# AD8402_WeinBridge_DCO.net
KiCad netlist of a schematic drawn in EAGLE
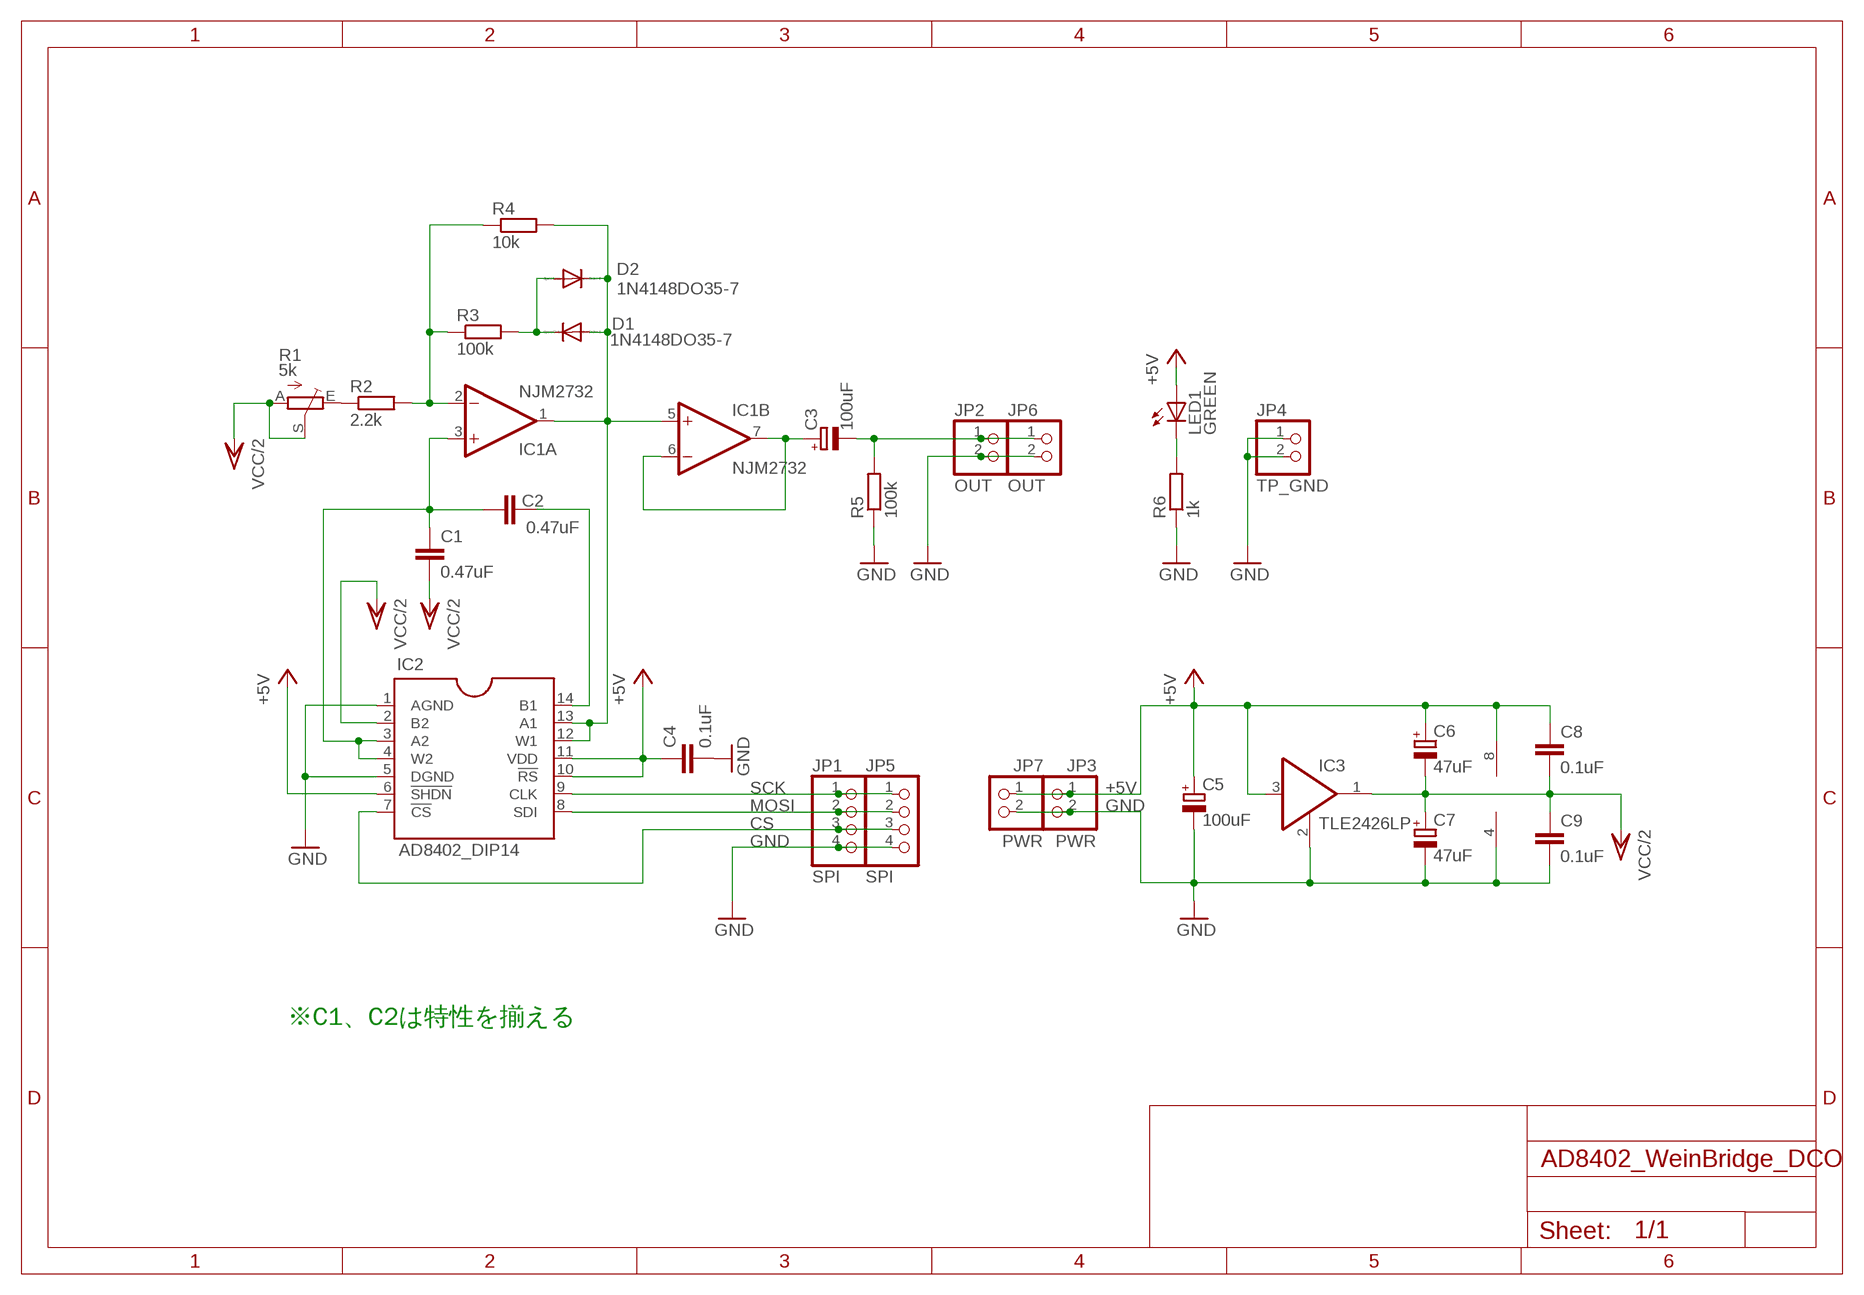
[diagram p0: schematic, sheet 1]

(export (version "E")
  (design (tool "Eeschema 10.0.6"))
  (components
    (comp (ref "C1")
      (value "0.47uF")
      (footprint "eagle-import:C050-035X075")
      (libsource (lib "eagle-import") (part "C-EU050-035X075"))
    )
    (comp (ref "C2")
      (value "0.47uF")
      (footprint "eagle-import:C050-035X075")
      (libsource (lib "eagle-import") (part "C-EU050-035X075"))
    )
    (comp (ref "C3")
      (value "100uF")
      (footprint "eagle-import:E2,5-7")
      (libsource (lib "eagle-import") (part "CPOL-EUE2.5-7"))
    )
    (comp (ref "C4")
      (value "0.1uF")
      (footprint "eagle-import:C025-024X044")
      (libsource (lib "eagle-import") (part "C-EU025-024X044"))
    )
    (comp (ref "C5")
      (value "100uF")
      (footprint "eagle-import:SANYO-OSCON_C6")
      (libsource (lib "eagle-import") (part "CPOL-EUSANYO_C6"))
    )
    (comp (ref "C6")
      (value "47uF")
      (footprint "eagle-import:E2,5-6")
      (libsource (lib "eagle-import") (part "CPOL-EUE2.5-6"))
    )
    (comp (ref "C7")
      (value "47uF")
      (footprint "eagle-import:E2,5-6")
      (libsource (lib "eagle-import") (part "CPOL-EUE2.5-6"))
    )
    (comp (ref "C8")
      (value "0.1uF")
      (footprint "eagle-import:C025-024X044")
      (libsource (lib "eagle-import") (part "C-EU025-024X044"))
    )
    (comp (ref "C9")
      (value "0.1uF")
      (footprint "eagle-import:C025-024X044")
      (libsource (lib "eagle-import") (part "C-EU025-024X044"))
    )
    (comp (ref "D1")
      (value "1N4148DO35-7")
      (footprint "eagle-import:DO35-7")
      (libsource (lib "eagle-import") (part "1N4148DO35-7"))
    )
    (comp (ref "D2")
      (value "1N4148DO35-7")
      (footprint "eagle-import:DO35-7")
      (libsource (lib "eagle-import") (part "1N4148DO35-7"))
    )
    (comp (ref "IC1")
      (value "NJM2732")
      (footprint "eagle-import:DIL08")
      (libsource (lib "eagle-import") (part "4558NLM"))
    )
    (comp (ref "IC2")
      (value "AD8402_DIP14")
      (footprint "eagle-import:AD8402_DIP14")
      (libsource (lib "eagle-import") (part "AD8402_DIP14"))
    )
    (comp (ref "IC3")
      (value "TLE2426LP")
      (footprint "eagle-import:TO226AA")
      (libsource (lib "eagle-import") (part "TLE2426LP"))
    )
    (comp (ref "JP1")
      (value "SPI")
      (footprint "eagle-import:1X04")
      (libsource (lib "eagle-import") (part "PINHD-1X4"))
    )
    (comp (ref "JP2")
      (value "OUT")
      (footprint "eagle-import:1X02")
      (libsource (lib "eagle-import") (part "PINHD-1X2"))
    )
    (comp (ref "JP3")
      (value "PWR")
      (footprint "eagle-import:1X02")
      (libsource (lib "eagle-import") (part "PINHD-1X2"))
    )
    (comp (ref "JP4")
      (value "TP_GND")
      (footprint "eagle-import:1X02")
      (libsource (lib "eagle-import") (part "PINHD-1X2"))
    )
    (comp (ref "JP5")
      (value "SPI")
      (footprint "eagle-import:1X04")
      (libsource (lib "eagle-import") (part "PINHD-1X4"))
    )
    (comp (ref "JP6")
      (value "OUT")
      (footprint "eagle-import:1X02")
      (libsource (lib "eagle-import") (part "PINHD-1X2"))
    )
    (comp (ref "JP7")
      (value "PWR")
      (footprint "eagle-import:1X02")
      (libsource (lib "eagle-import") (part "PINHD-1X2"))
    )
    (comp (ref "LED1")
      (value "GREEN")
      (footprint "eagle-import:LED3MM")
      (libsource (lib "eagle-import") (part "LED3MM"))
    )
    (comp (ref "R1")
      (value "5k")
      (footprint "eagle-import:B25P")
      (libsource (lib "eagle-import") (part "TRIM_EU-B25P"))
    )
    (comp (ref "R2")
      (value "2.2k")
      (footprint "eagle-import:0207_7")
      (libsource (lib "eagle-import") (part "R-EU_0207/7"))
    )
    (comp (ref "R3")
      (value "100k")
      (footprint "eagle-import:0207_7")
      (libsource (lib "eagle-import") (part "R-EU_0207/7"))
    )
    (comp (ref "R4")
      (value "10k")
      (footprint "eagle-import:0207_7")
      (libsource (lib "eagle-import") (part "R-EU_0207/7"))
    )
    (comp (ref "R5")
      (value "100k")
      (footprint "eagle-import:0207_7")
      (libsource (lib "eagle-import") (part "R-EU_0207/7"))
    )
    (comp (ref "R6")
      (value "1k")
      (footprint "eagle-import:0207_7")
      (libsource (lib "eagle-import") (part "R-EU_0207/7"))
    )
  )
  (nets
    (net (code "1") (name "+5V") (class "Default")
      (node (ref "C4") (pin "1") (pinfunction "1_1") (pintype "passive"))
      (node (ref "C5") (pin "+") (pinfunction "+_+") (pintype "passive"))
      (node (ref "C6") (pin "+") (pinfunction "+_+") (pintype "passive"))
      (node (ref "C8") (pin "1") (pinfunction "1_1") (pintype "passive"))
      (node (ref "IC1") (pin "8") (pinfunction "V+_8") (pintype "power_in"))
      (node (ref "IC2") (pin "10") (pinfunction "~{RS}_10") (pintype "input"))
      (node (ref "IC2") (pin "11") (pinfunction "VDD_11") (pintype "power_in"))
      (node (ref "IC2") (pin "6") (pinfunction "~{SHDN}_6") (pintype "input"))
      (node (ref "IC3") (pin "3") (pinfunction "I_3") (pintype "input"))
      (node (ref "JP3") (pin "1") (pinfunction "1_1") (pintype "passive"))
      (node (ref "JP7") (pin "1") (pinfunction "1_1") (pintype "passive"))
      (node (ref "LED1") (pin "A") (pinfunction "A_A") (pintype "passive"))
    )
    (net (code "2") (name "/CS") (class "Default")
      (node (ref "IC2") (pin "7") (pinfunction "~{CS}_7") (pintype "input"))
      (node (ref "JP1") (pin "3") (pinfunction "3_3") (pintype "passive"))
      (node (ref "JP5") (pin "3") (pinfunction "3_3") (pintype "passive"))
    )
    (net (code "3") (name "/MOSI") (class "Default")
      (node (ref "IC2") (pin "8") (pinfunction "SDI_8") (pintype "input"))
      (node (ref "JP1") (pin "2") (pinfunction "2_2") (pintype "passive"))
      (node (ref "JP5") (pin "2") (pinfunction "2_2") (pintype "passive"))
    )
    (net (code "4") (name "/SCK") (class "Default")
      (node (ref "IC2") (pin "9") (pinfunction "CLK_9") (pintype "input"))
      (node (ref "JP1") (pin "1") (pinfunction "1_1") (pintype "passive"))
      (node (ref "JP5") (pin "1") (pinfunction "1_1") (pintype "passive"))
    )
    (net (code "5") (name "GND") (class "Default")
      (node (ref "C4") (pin "2") (pinfunction "2_2") (pintype "passive"))
      (node (ref "C5") (pin "-") (pinfunction "-_-") (pintype "passive"))
      (node (ref "C7") (pin "-") (pinfunction "-_-") (pintype "passive"))
      (node (ref "C9") (pin "2") (pinfunction "2_2") (pintype "passive"))
      (node (ref "IC1") (pin "4") (pinfunction "V-_4") (pintype "power_in"))
      (node (ref "IC2") (pin "1") (pinfunction "AGND_1") (pintype "power_in"))
      (node (ref "IC2") (pin "5") (pinfunction "DGND_5") (pintype "power_in"))
      (node (ref "IC3") (pin "2") (pinfunction "P$1_2") (pintype "power_in"))
      (node (ref "JP1") (pin "4") (pinfunction "4_4") (pintype "passive"))
      (node (ref "JP2") (pin "2") (pinfunction "2_2") (pintype "passive"))
      (node (ref "JP3") (pin "2") (pinfunction "2_2") (pintype "passive"))
      (node (ref "JP4") (pin "1") (pinfunction "1_1") (pintype "passive"))
      (node (ref "JP4") (pin "2") (pinfunction "2_2") (pintype "passive"))
      (node (ref "JP5") (pin "4") (pinfunction "4_4") (pintype "passive"))
      (node (ref "JP6") (pin "2") (pinfunction "2_2") (pintype "passive"))
      (node (ref "JP7") (pin "2") (pinfunction "2_2") (pintype "passive"))
      (node (ref "R5") (pin "1") (pinfunction "1_1") (pintype "passive"))
      (node (ref "R6") (pin "1") (pinfunction "1_1") (pintype "passive"))
    )
    (net (code "6") (name "Net-(C3-Pad-)") (class "Default")
      (node (ref "C3") (pin "-") (pinfunction "-_-") (pintype "passive"))
      (node (ref "JP2") (pin "1") (pinfunction "1_1") (pintype "passive"))
      (node (ref "JP6") (pin "1") (pinfunction "1_1") (pintype "passive"))
      (node (ref "R5") (pin "2") (pinfunction "2_2") (pintype "passive"))
    )
    (net (code "7") (name "Net-(D1-PadC)") (class "Default")
      (node (ref "D1") (pin "C") (pinfunction "C_C") (pintype "passive"))
      (node (ref "D2") (pin "A") (pinfunction "A_A") (pintype "passive"))
      (node (ref "R3") (pin "2") (pinfunction "2_2") (pintype "passive"))
    )
    (net (code "8") (name "Net-(IC1A-+IN)") (class "Default")
      (node (ref "C1") (pin "1") (pinfunction "1_1") (pintype "passive"))
      (node (ref "C2") (pin "1") (pinfunction "1_1") (pintype "passive"))
      (node (ref "IC1") (pin "3") (pinfunction "+IN_3") (pintype "input"))
      (node (ref "IC2") (pin "3") (pinfunction "A2_3") (pintype "passive"))
      (node (ref "IC2") (pin "4") (pinfunction "W2_4") (pintype "passive"))
    )
    (net (code "9") (name "Net-(IC1A--IN)") (class "Default")
      (node (ref "IC1") (pin "2") (pinfunction "-IN_2") (pintype "input"))
      (node (ref "R2") (pin "2") (pinfunction "2_2") (pintype "passive"))
      (node (ref "R3") (pin "1") (pinfunction "1_1") (pintype "passive"))
      (node (ref "R4") (pin "1") (pinfunction "1_1") (pintype "passive"))
    )
    (net (code "10") (name "Net-(IC1A-OUT)") (class "Default")
      (node (ref "D1") (pin "A") (pinfunction "A_A") (pintype "passive"))
      (node (ref "D2") (pin "C") (pinfunction "C_C") (pintype "passive"))
      (node (ref "IC1") (pin "1") (pinfunction "OUT_1") (pintype "output"))
      (node (ref "IC1") (pin "5") (pinfunction "+IN_5") (pintype "input"))
      (node (ref "IC2") (pin "12") (pinfunction "W1_12") (pintype "passive"))
      (node (ref "IC2") (pin "13") (pinfunction "A1_13") (pintype "passive"))
      (node (ref "R4") (pin "2") (pinfunction "2_2") (pintype "passive"))
    )
    (net (code "11") (name "Net-(IC1B--IN)") (class "Default")
      (node (ref "C3") (pin "+") (pinfunction "+_+") (pintype "passive"))
      (node (ref "IC1") (pin "6") (pinfunction "-IN_6") (pintype "input"))
      (node (ref "IC1") (pin "7") (pinfunction "OUT_7") (pintype "output"))
    )
    (net (code "12") (name "Net-(IC2-B1)") (class "Default")
      (node (ref "C2") (pin "2") (pinfunction "2_2") (pintype "passive"))
      (node (ref "IC2") (pin "14") (pinfunction "B1_14") (pintype "passive"))
    )
    (net (code "13") (name "Net-(LED1-C)") (class "Default")
      (node (ref "LED1") (pin "K") (pinfunction "C_K") (pintype "passive"))
      (node (ref "R6") (pin "2") (pinfunction "2_2") (pintype "passive"))
    )
    (net (code "14") (name "Net-(R1-PadE)") (class "Default")
      (node (ref "R1") (pin "E") (pinfunction "E_E") (pintype "passive"))
      (node (ref "R2") (pin "1") (pinfunction "1_1") (pintype "passive"))
    )
    (net (code "15") (name "VCC{slash}2") (class "Default")
      (node (ref "C1") (pin "2") (pinfunction "2_2") (pintype "passive"))
      (node (ref "C6") (pin "-") (pinfunction "-_-") (pintype "passive"))
      (node (ref "C7") (pin "+") (pinfunction "+_+") (pintype "passive"))
      (node (ref "C8") (pin "2") (pinfunction "2_2") (pintype "passive"))
      (node (ref "C9") (pin "1") (pinfunction "1_1") (pintype "passive"))
      (node (ref "IC2") (pin "2") (pinfunction "B2_2") (pintype "passive"))
      (node (ref "IC3") (pin "1") (pinfunction "O_1") (pintype "open_collector"))
      (node (ref "R1") (pin "A") (pinfunction "A_A") (pintype "passive"))
      (node (ref "R1") (pin "S") (pinfunction "S_S") (pintype "passive"))
    )
  )
)
